# Coulomb_Counter_Test_Board.net
KiCad netlist of a schematic drawn in EAGLE
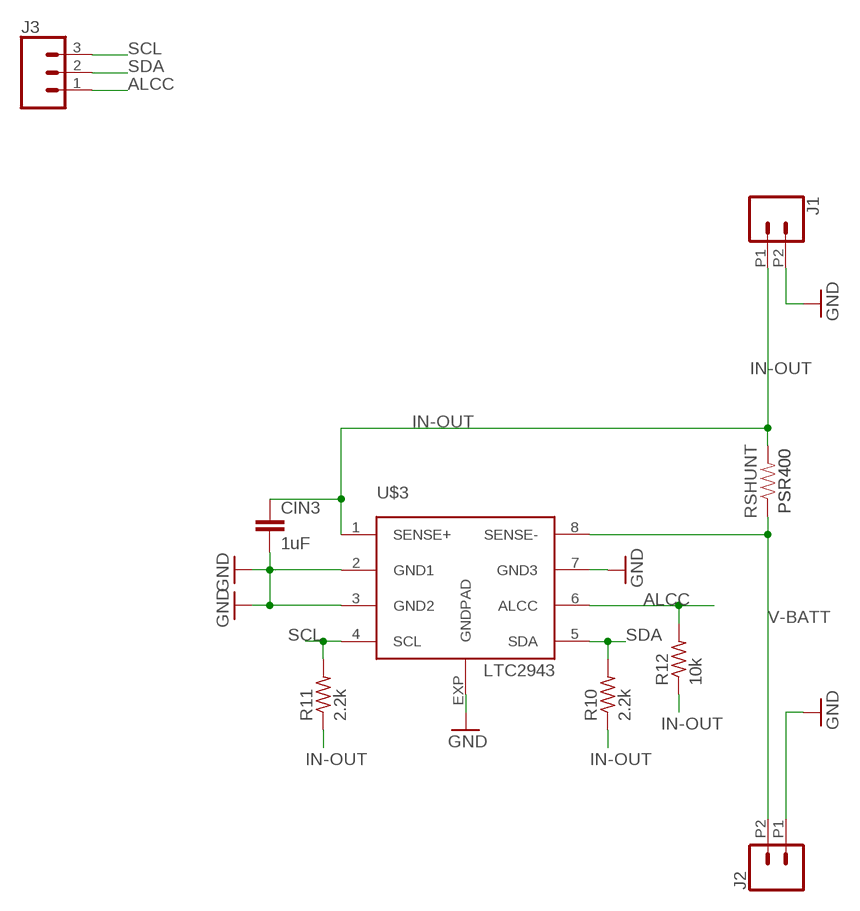
[diagram p0: schematic, sheet 1]

(export (version "E")
  (design (tool "Eeschema 10.0.6"))
  (components
    (comp (ref "CIN3")
      (value "1uF")
      (footprint "eagle-import:0402-CAP")
      (libsource (lib "eagle-import") (part ".1UF-CER"))
    )
    (comp (ref "J1")
      (value "CONN_022.54MM_SCREWTERM")
      (footprint "eagle-import:1X02_2.54_SCREWTERM")
      (libsource (lib "eagle-import") (part "CONN_022.54MM_SCREWTERM"))
    )
    (comp (ref "J2")
      (value "CONN_022.54MM_SCREWTERM")
      (footprint "eagle-import:1X02_2.54_SCREWTERM")
      (libsource (lib "eagle-import") (part "CONN_022.54MM_SCREWTERM"))
    )
    (comp (ref "J3")
      (value "CONN_03")
      (footprint "eagle-import:1X03")
      (libsource (lib "eagle-import") (part "CONN_03"))
    )
    (comp (ref "R10")
      (value "2.2k")
      (footprint "eagle-import:R0805")
      (libsource (lib "eagle-import") (part "R-US_R0805"))
    )
    (comp (ref "R11")
      (value "2.2k")
      (footprint "eagle-import:R0805")
      (libsource (lib "eagle-import") (part "R-US_R0805"))
    )
    (comp (ref "R12")
      (value "10k")
      (footprint "eagle-import:R0805")
      (libsource (lib "eagle-import") (part "R-US_R0805"))
    )
    (comp (ref "RSHUNT")
      (value "PSR400")
      (footprint "eagle-import:PSR400")
      (libsource (lib "eagle-import") (part "PSR400"))
    )
    (comp (ref "U$3")
      (value "LTC2943")
      (footprint "eagle-import:DFN8(3X3)LT")
      (libsource (lib "eagle-import") (part "LTC2943"))
    )
  )
  (nets
    (net (code "1") (name "/ALCC") (class "Default")
      (node (ref "J3") (pin "1") (pinfunction "1_1") (pintype "passive"))
      (node (ref "R12") (pin "2") (pinfunction "2_2") (pintype "passive"))
      (node (ref "U$3") (pin "6") (pinfunction "ALCC_6") (pintype "bidirectional"))
    )
    (net (code "2") (name "/IN-OUT") (class "Default")
      (node (ref "CIN3") (pin "1") (pinfunction "1_1") (pintype "passive"))
      (node (ref "J1") (pin "P1") (pinfunction "1_P1") (pintype "passive"))
      (node (ref "R10") (pin "1") (pinfunction "1_1") (pintype "passive"))
      (node (ref "R11") (pin "1") (pinfunction "1_1") (pintype "passive"))
      (node (ref "R12") (pin "1") (pinfunction "1_1") (pintype "passive"))
      (node (ref "RSHUNT") (pin "P$2") (pinfunction "2_P$2") (pintype "passive"))
      (node (ref "U$3") (pin "1") (pinfunction "SENSE+_1") (pintype "bidirectional"))
    )
    (net (code "3") (name "/SCL") (class "Default")
      (node (ref "J3") (pin "3") (pinfunction "3_3") (pintype "passive"))
      (node (ref "R11") (pin "2") (pinfunction "2_2") (pintype "passive"))
      (node (ref "U$3") (pin "4") (pinfunction "SCL_4") (pintype "bidirectional"))
    )
    (net (code "4") (name "/SDA") (class "Default")
      (node (ref "J3") (pin "2") (pinfunction "2_2") (pintype "passive"))
      (node (ref "R10") (pin "2") (pinfunction "2_2") (pintype "passive"))
      (node (ref "U$3") (pin "5") (pinfunction "SDA_5") (pintype "bidirectional"))
    )
    (net (code "5") (name "/V-BATT") (class "Default")
      (node (ref "J2") (pin "P2") (pinfunction "2_P2") (pintype "passive"))
      (node (ref "RSHUNT") (pin "P$1") (pinfunction "1_P$1") (pintype "passive"))
      (node (ref "U$3") (pin "8") (pinfunction "SENSE-_8") (pintype "bidirectional"))
    )
    (net (code "6") (name "GND") (class "Default")
      (node (ref "CIN3") (pin "2") (pinfunction "2_2") (pintype "passive"))
      (node (ref "J1") (pin "P2") (pinfunction "2_P2") (pintype "passive"))
      (node (ref "J2") (pin "P1") (pinfunction "1_P1") (pintype "passive"))
      (node (ref "U$3") (pin "2") (pinfunction "GND1_2") (pintype "bidirectional"))
      (node (ref "U$3") (pin "3") (pinfunction "GND2_3") (pintype "bidirectional"))
      (node (ref "U$3") (pin "7") (pinfunction "GND3_7") (pintype "bidirectional"))
      (node (ref "U$3") (pin "EXP") (pinfunction "GNDPAD_EXP") (pintype "bidirectional"))
    )
  )
)
